# PCB.net
KiCad netlist of a schematic drawn in EAGLE
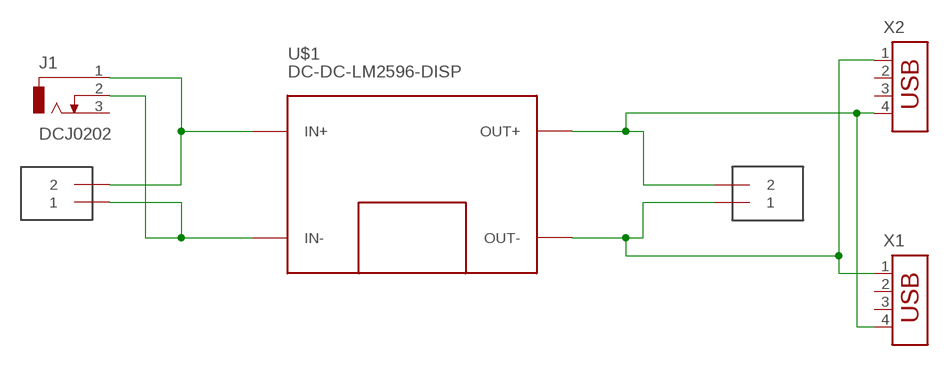
[diagram p0: schematic, sheet 1]

(export (version "E")
  (design (tool "Eeschema 10.0.6"))
  (components
    (comp (ref "J1")
      (value "DCJ0202")
      (footprint "eagle-import:DCJ0202")
      (libsource (lib "eagle-import") (part "DCJ0202"))
    )
    (comp (ref "U$1")
      (value "DC-DC-LM2596-DISP")
      (footprint "eagle-import:DC-DC-LM2596-DISP")
      (libsource (lib "eagle-import") (part "DC-DC-LM2596-DISP"))
    )
    (comp (ref "U$2")
      (value "TERMINAL_2P")
      (footprint "eagle-import:KF301-2P")
      (libsource (lib "eagle-import") (part "TERMINAL_2P"))
    )
    (comp (ref "U$3")
      (value "TERMINAL_2P")
      (footprint "eagle-import:KF301-2P")
      (libsource (lib "eagle-import") (part "TERMINAL_2P"))
    )
    (comp (ref "X1")
      (value "USB-787616")
      (footprint "eagle-import:USB")
      (libsource (lib "eagle-import") (part "USB-787616"))
    )
    (comp (ref "X2")
      (value "USB-787616")
      (footprint "eagle-import:USB")
      (libsource (lib "eagle-import") (part "USB-787616"))
    )
  )
  (nets
    (net (code "1") (name "Net-(J1-Pad1)") (class "Default")
      (node (ref "J1") (pin "1") (pinfunction "1_1") (pintype "passive"))
      (node (ref "U$1") (pin "IN+") (pinfunction "IN+_IN+") (pintype "bidirectional"))
      (node (ref "U$2") (pin "2") (pinfunction "2_2") (pintype "bidirectional"))
    )
    (net (code "2") (name "Net-(J1-Pad2)") (class "Default")
      (node (ref "J1") (pin "2") (pinfunction "2_2") (pintype "passive"))
      (node (ref "U$1") (pin "IN-") (pinfunction "IN-_IN-") (pintype "bidirectional"))
      (node (ref "U$2") (pin "1") (pinfunction "1_1") (pintype "bidirectional"))
    )
    (net (code "3") (name "Net-(U$1-PadOUT+)") (class "Default")
      (node (ref "U$1") (pin "OUT+") (pinfunction "OUT+_OUT+") (pintype "bidirectional"))
      (node (ref "U$3") (pin "2") (pinfunction "2_2") (pintype "bidirectional"))
      (node (ref "X1") (pin "4") (pinfunction "4_4") (pintype "passive"))
      (node (ref "X2") (pin "4") (pinfunction "4_4") (pintype "passive"))
    )
    (net (code "4") (name "Net-(U$1-PadOUT-)") (class "Default")
      (node (ref "U$1") (pin "OUT-") (pinfunction "OUT-_OUT-") (pintype "bidirectional"))
      (node (ref "U$3") (pin "1") (pinfunction "1_1") (pintype "bidirectional"))
      (node (ref "X1") (pin "1") (pinfunction "1_1") (pintype "passive"))
      (node (ref "X2") (pin "1") (pinfunction "1_1") (pintype "passive"))
    )
    (net (code "5") (name "unconnected-(J1-Pad3)") (class "Default")
      (node (ref "J1") (pin "3") (pinfunction "3_3") (pintype "passive"))
    )
    (net (code "6") (name "unconnected-(X1-Pad2)") (class "Default")
      (node (ref "X1") (pin "2") (pinfunction "2_2") (pintype "passive"))
    )
    (net (code "7") (name "unconnected-(X1-Pad3)") (class "Default")
      (node (ref "X1") (pin "3") (pinfunction "3_3") (pintype "passive"))
    )
    (net (code "8") (name "unconnected-(X2-Pad2)") (class "Default")
      (node (ref "X2") (pin "2") (pinfunction "2_2") (pintype "passive"))
    )
    (net (code "9") (name "unconnected-(X2-Pad3)") (class "Default")
      (node (ref "X2") (pin "3") (pinfunction "3_3") (pintype "passive"))
    )
  )
)
